# Traszka.net
KiCad netlist of a schematic drawn in EAGLE
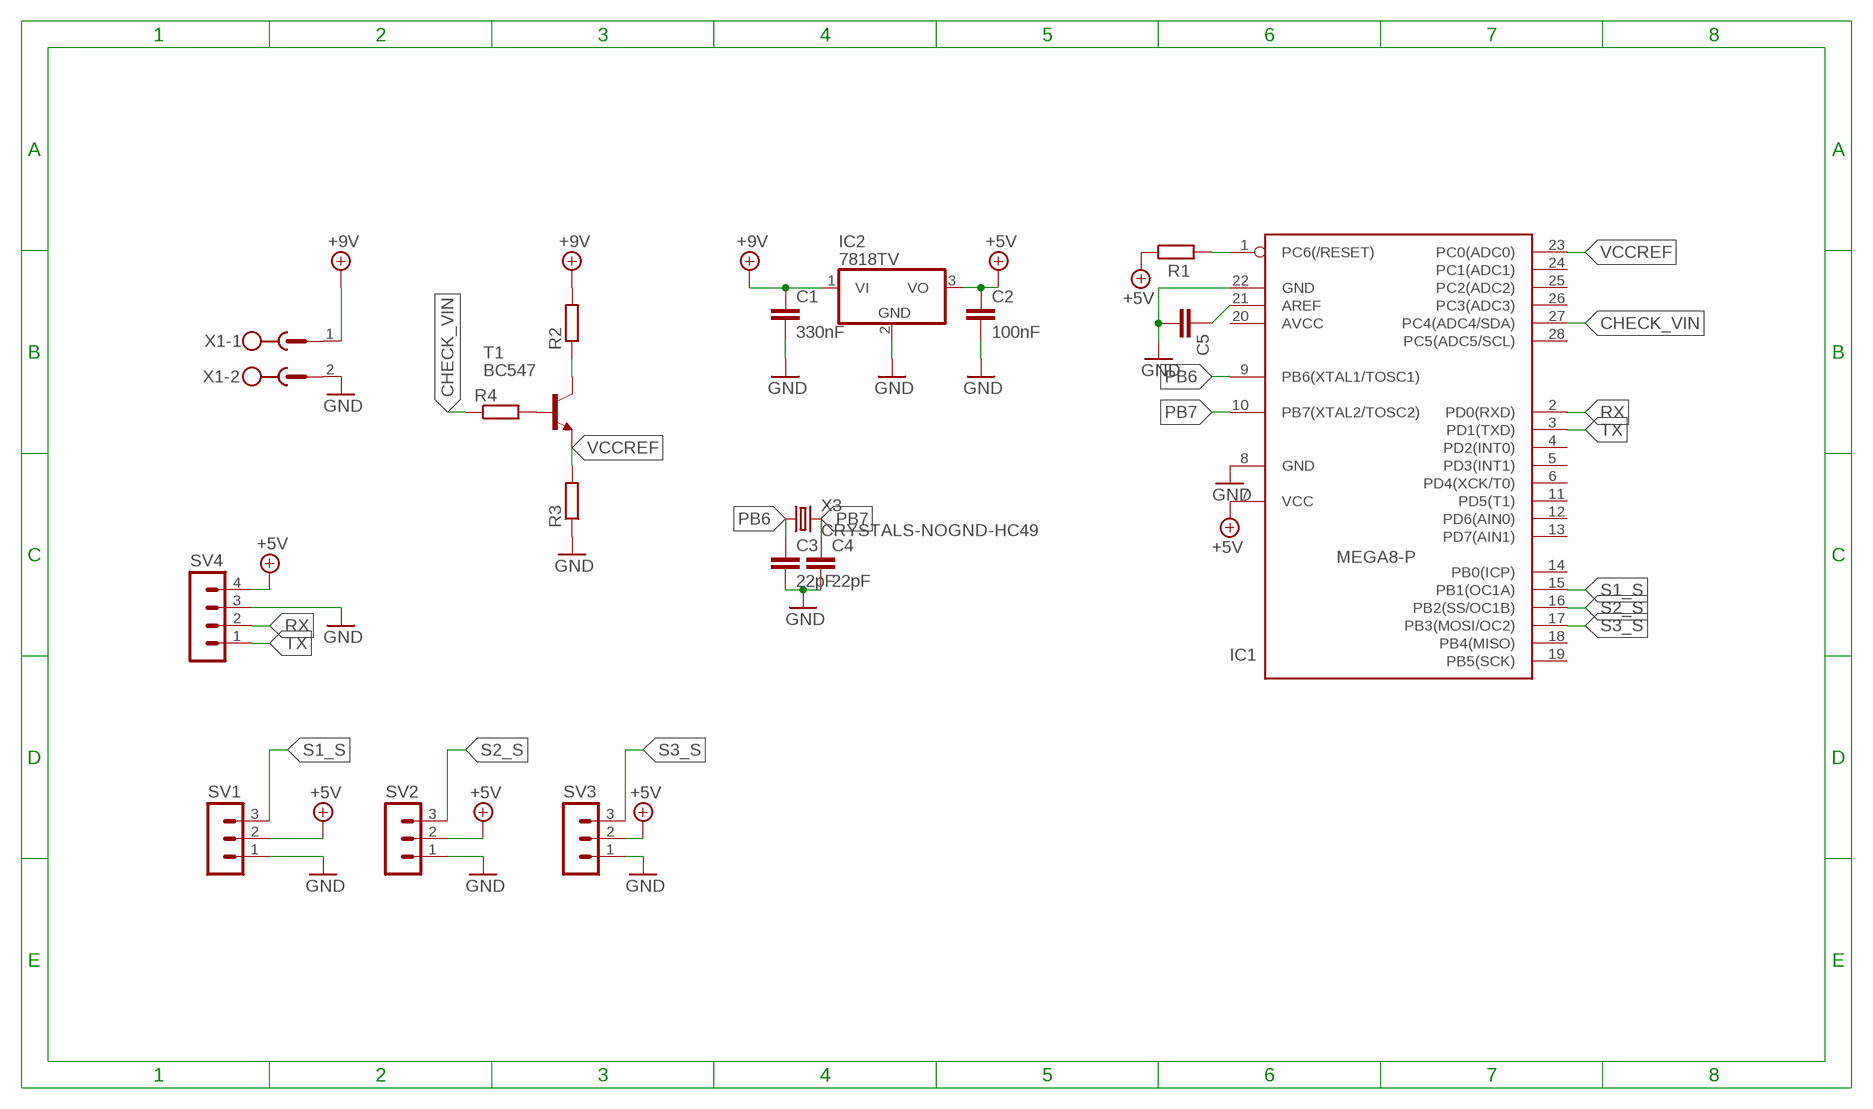
[diagram p0: schematic, sheet 1]

(export (version "E")
  (design (tool "Eeschema 10.0.6"))
  (components
    (comp (ref "C1")
      (value "330nF")
      (footprint "eagle-import:C050-024X044")
      (libsource (lib "eagle-import") (part "C-EU050-024X044"))
    )
    (comp (ref "C2")
      (value "100nF")
      (footprint "eagle-import:C050-024X044")
      (libsource (lib "eagle-import") (part "C-EU050-024X044"))
    )
    (comp (ref "C3")
      (value "22pF")
      (footprint "eagle-import:C050-024X044")
      (libsource (lib "eagle-import") (part "C-EU050-024X044"))
    )
    (comp (ref "C4")
      (value "22pF")
      (footprint "eagle-import:C050-024X044")
      (libsource (lib "eagle-import") (part "C-EU050-024X044"))
    )
    (comp (ref "C5")
      (value "C-EU050-024X044")
      (footprint "eagle-import:C050-024X044")
      (libsource (lib "eagle-import") (part "C-EU050-024X044"))
    )
    (comp (ref "IC1")
      (value "MEGA8-P")
      (footprint "eagle-import:DIL28-3")
      (libsource (lib "eagle-import") (part "MEGA8-P"))
    )
    (comp (ref "IC2")
      (value "7818TV")
      (footprint "eagle-import:TO220V")
      (libsource (lib "eagle-import") (part "78TV18"))
    )
    (comp (ref "R1")
      (value "R-EU_0204/7")
      (footprint "eagle-import:0204_7")
      (libsource (lib "eagle-import") (part "R-EU_0204/7"))
    )
    (comp (ref "R2")
      (value "R-EU_0204/7")
      (footprint "eagle-import:0204_7")
      (libsource (lib "eagle-import") (part "R-EU_0204/7"))
    )
    (comp (ref "R3")
      (value "R-EU_0204/5")
      (footprint "eagle-import:0204_5")
      (libsource (lib "eagle-import") (part "R-EU_0204/5"))
    )
    (comp (ref "R4")
      (value "R-EU_0204/7")
      (footprint "eagle-import:0204_7")
      (libsource (lib "eagle-import") (part "R-EU_0204/7"))
    )
    (comp (ref "SV1")
      (value "MA03-1")
      (footprint "eagle-import:MA03-1")
      (libsource (lib "eagle-import") (part "MA03-1"))
    )
    (comp (ref "SV2")
      (value "MA03-1")
      (footprint "eagle-import:MA03-1")
      (libsource (lib "eagle-import") (part "MA03-1"))
    )
    (comp (ref "SV3")
      (value "MA03-1")
      (footprint "eagle-import:MA03-1")
      (libsource (lib "eagle-import") (part "MA03-1"))
    )
    (comp (ref "SV4")
      (value "MA04-1")
      (footprint "eagle-import:MA04-1")
      (libsource (lib "eagle-import") (part "MA04-1"))
    )
    (comp (ref "T1")
      (value "BC547")
      (footprint "eagle-import:TO92")
      (libsource (lib "eagle-import") (part "BC547"))
    )
    (comp (ref "X1")
      (value "MSTBV2")
      (footprint "eagle-import:MSTBV2")
      (libsource (lib "eagle-import") (part "MSTBV2"))
    )
    (comp (ref "X3")
      (value "CRYSTALS-NOGND-HC49")
      (footprint "eagle-import:HC49")
      (libsource (lib "eagle-import") (part "CRYSTALS-NOGND-HC49"))
    )
  )
  (nets
    (net (code "1") (name "+5V") (class "Default")
      (node (ref "C2") (pin "1") (pinfunction "1_1") (pintype "passive"))
      (node (ref "IC1") (pin "7") (pinfunction "VCC_7") (pintype "power_in"))
      (node (ref "IC2") (pin "3") (pinfunction "VO_3") (pintype "passive"))
      (node (ref "R1") (pin "1") (pinfunction "1_1") (pintype "passive"))
      (node (ref "SV1") (pin "2") (pinfunction "2_2") (pintype "passive"))
      (node (ref "SV2") (pin "2") (pinfunction "2_2") (pintype "passive"))
      (node (ref "SV3") (pin "2") (pinfunction "2_2") (pintype "passive"))
      (node (ref "SV4") (pin "4") (pinfunction "4_4") (pintype "passive"))
    )
    (net (code "2") (name "+9V") (class "Default")
      (node (ref "C1") (pin "1") (pinfunction "1_1") (pintype "passive"))
      (node (ref "IC2") (pin "1") (pinfunction "VI_1") (pintype "input"))
      (node (ref "R2") (pin "2") (pinfunction "2_2") (pintype "passive"))
      (node (ref "X1") (pin "1") (pinfunction "SK_1") (pintype "passive"))
    )
    (net (code "3") (name "/AVCC") (class "Default")
      (node (ref "IC1") (pin "20") (pinfunction "AVCC_20") (pintype "power_in"))
    )
    (net (code "4") (name "CHECK_VIN") (class "Default")
      (node (ref "IC1") (pin "27") (pinfunction "PC4(ADC4/SDA)_27") (pintype "bidirectional"))
      (node (ref "R4") (pin "1") (pinfunction "1_1") (pintype "passive"))
    )
    (net (code "5") (name "GND") (class "Default")
      (node (ref "C1") (pin "2") (pinfunction "2_2") (pintype "passive"))
      (node (ref "C2") (pin "2") (pinfunction "2_2") (pintype "passive"))
      (node (ref "C3") (pin "2") (pinfunction "2_2") (pintype "passive"))
      (node (ref "C4") (pin "2") (pinfunction "2_2") (pintype "passive"))
      (node (ref "C5") (pin "2") (pinfunction "2_2") (pintype "passive"))
      (node (ref "IC1") (pin "22") (pinfunction "GND_22") (pintype "power_in"))
      (node (ref "IC1") (pin "8") (pinfunction "GND_8") (pintype "power_in"))
      (node (ref "IC2") (pin "2") (pinfunction "GND_2") (pintype "passive"))
      (node (ref "R3") (pin "1") (pinfunction "1_1") (pintype "passive"))
      (node (ref "SV1") (pin "1") (pinfunction "1_1") (pintype "passive"))
      (node (ref "SV2") (pin "1") (pinfunction "1_1") (pintype "passive"))
      (node (ref "SV3") (pin "1") (pinfunction "1_1") (pintype "passive"))
      (node (ref "SV4") (pin "3") (pinfunction "3_3") (pintype "passive"))
      (node (ref "X1") (pin "2") (pinfunction "SK_2") (pintype "passive"))
    )
    (net (code "6") (name "Net-(IC1-AREF)") (class "Default")
      (node (ref "C5") (pin "1") (pinfunction "1_1") (pintype "passive"))
      (node (ref "IC1") (pin "21") (pinfunction "AREF_21") (pintype "passive"))
    )
    (net (code "7") (name "Net-(IC1-PC6({slash}RESET))") (class "Default")
      (node (ref "IC1") (pin "1") (pinfunction "PC6(/RESET)_1") (pintype "bidirectional"))
      (node (ref "R1") (pin "2") (pinfunction "2_2") (pintype "passive"))
    )
    (net (code "8") (name "Net-(T1-B)") (class "Default")
      (node (ref "R4") (pin "2") (pinfunction "2_2") (pintype "passive"))
      (node (ref "T1") (pin "2") (pinfunction "B_2") (pintype "passive"))
    )
    (net (code "9") (name "Net-(T1-C)") (class "Default")
      (node (ref "R2") (pin "1") (pinfunction "1_1") (pintype "passive"))
      (node (ref "T1") (pin "3") (pinfunction "C_3") (pintype "passive"))
    )
    (net (code "10") (name "PB6") (class "Default")
      (node (ref "C3") (pin "1") (pinfunction "1_1") (pintype "passive"))
      (node (ref "IC1") (pin "9") (pinfunction "PB6(XTAL1/TOSC1)_9") (pintype "bidirectional"))
      (node (ref "X3") (pin "1") (pinfunction "1_1") (pintype "passive"))
    )
    (net (code "11") (name "PB7") (class "Default")
      (node (ref "C4") (pin "1") (pinfunction "1_1") (pintype "passive"))
      (node (ref "IC1") (pin "10") (pinfunction "PB7(XTAL2/TOSC2)_10") (pintype "bidirectional"))
      (node (ref "X3") (pin "2") (pinfunction "2_2") (pintype "passive"))
    )
    (net (code "12") (name "RX") (class "Default")
      (node (ref "IC1") (pin "2") (pinfunction "PD0(RXD)_2") (pintype "bidirectional"))
      (node (ref "SV4") (pin "2") (pinfunction "2_2") (pintype "passive"))
    )
    (net (code "13") (name "S1_S") (class "Default")
      (node (ref "IC1") (pin "15") (pinfunction "PB1(OC1A)_15") (pintype "bidirectional"))
      (node (ref "SV1") (pin "3") (pinfunction "3_3") (pintype "passive"))
    )
    (net (code "14") (name "S2_S") (class "Default")
      (node (ref "IC1") (pin "16") (pinfunction "PB2(SS/OC1B)_16") (pintype "bidirectional"))
      (node (ref "SV2") (pin "3") (pinfunction "3_3") (pintype "passive"))
    )
    (net (code "15") (name "S3_S") (class "Default")
      (node (ref "IC1") (pin "17") (pinfunction "PB3(MOSI/OC2)_17") (pintype "bidirectional"))
      (node (ref "SV3") (pin "3") (pinfunction "3_3") (pintype "passive"))
    )
    (net (code "16") (name "TX") (class "Default")
      (node (ref "IC1") (pin "3") (pinfunction "PD1(TXD)_3") (pintype "bidirectional"))
      (node (ref "SV4") (pin "1") (pinfunction "1_1") (pintype "passive"))
    )
    (net (code "17") (name "VCCREF") (class "Default")
      (node (ref "IC1") (pin "23") (pinfunction "PC0(ADC0)_23") (pintype "bidirectional"))
      (node (ref "R3") (pin "2") (pinfunction "2_2") (pintype "passive"))
      (node (ref "T1") (pin "1") (pinfunction "E_1") (pintype "passive"))
    )
    (net (code "18") (name "unconnected-(IC1-PB0(ICP)-Pad14)") (class "Default")
      (node (ref "IC1") (pin "14") (pinfunction "PB0(ICP)_14") (pintype "bidirectional"))
    )
    (net (code "19") (name "unconnected-(IC1-PB4(MISO)-Pad18)") (class "Default")
      (node (ref "IC1") (pin "18") (pinfunction "PB4(MISO)_18") (pintype "bidirectional"))
    )
    (net (code "20") (name "unconnected-(IC1-PB5(SCK)-Pad19)") (class "Default")
      (node (ref "IC1") (pin "19") (pinfunction "PB5(SCK)_19") (pintype "bidirectional"))
    )
    (net (code "21") (name "unconnected-(IC1-PC1(ADC1)-Pad24)") (class "Default")
      (node (ref "IC1") (pin "24") (pinfunction "PC1(ADC1)_24") (pintype "bidirectional"))
    )
    (net (code "22") (name "unconnected-(IC1-PC2(ADC2)-Pad25)") (class "Default")
      (node (ref "IC1") (pin "25") (pinfunction "PC2(ADC2)_25") (pintype "bidirectional"))
    )
    (net (code "23") (name "unconnected-(IC1-PC3(ADC3)-Pad26)") (class "Default")
      (node (ref "IC1") (pin "26") (pinfunction "PC3(ADC3)_26") (pintype "bidirectional"))
    )
    (net (code "24") (name "unconnected-(IC1-PC5(ADC5{slash}SCL)-Pad28)") (class "Default")
      (node (ref "IC1") (pin "28") (pinfunction "PC5(ADC5/SCL)_28") (pintype "bidirectional"))
    )
    (net (code "25") (name "unconnected-(IC1-PD2(INT0)-Pad4)") (class "Default")
      (node (ref "IC1") (pin "4") (pinfunction "PD2(INT0)_4") (pintype "bidirectional"))
    )
    (net (code "26") (name "unconnected-(IC1-PD3(INT1)-Pad5)") (class "Default")
      (node (ref "IC1") (pin "5") (pinfunction "PD3(INT1)_5") (pintype "bidirectional"))
    )
    (net (code "27") (name "unconnected-(IC1-PD4(XCK{slash}T0)-Pad6)") (class "Default")
      (node (ref "IC1") (pin "6") (pinfunction "PD4(XCK/T0)_6") (pintype "bidirectional"))
    )
    (net (code "28") (name "unconnected-(IC1-PD5(T1)-Pad11)") (class "Default")
      (node (ref "IC1") (pin "11") (pinfunction "PD5(T1)_11") (pintype "bidirectional"))
    )
    (net (code "29") (name "unconnected-(IC1-PD6(AIN0)-Pad12)") (class "Default")
      (node (ref "IC1") (pin "12") (pinfunction "PD6(AIN0)_12") (pintype "bidirectional"))
    )
    (net (code "30") (name "unconnected-(IC1-PD7(AIN1)-Pad13)") (class "Default")
      (node (ref "IC1") (pin "13") (pinfunction "PD7(AIN1)_13") (pintype "bidirectional"))
    )
  )
)
